# untitled.net
KiCad netlist of a schematic drawn in EAGLE
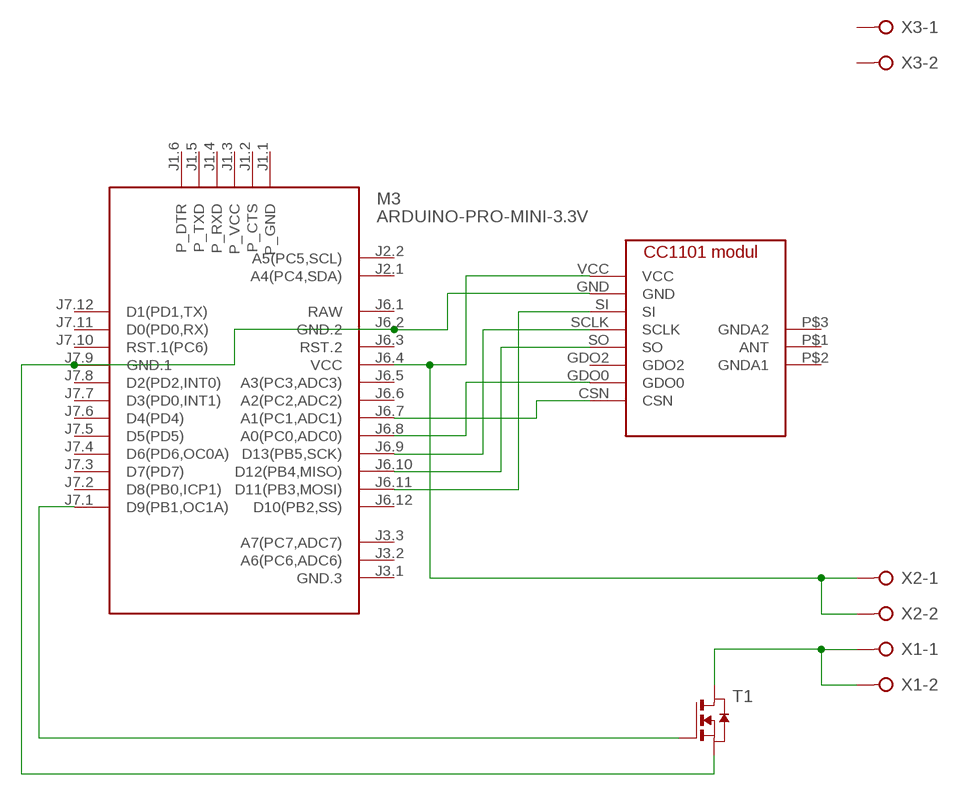
[diagram p0: schematic, sheet 1]

(export (version "E")
  (design (tool "Eeschema 10.0.6"))
  (components
    (comp (ref "M3")
      (value "ARDUINO-PRO-MINI-3.3V")
      (footprint "eagle-import:ARDUINO-PRO-MINI")
      (libsource (lib "eagle-import") (part "ARDUINO-PRO-MINI-3.3V"))
    )
    (comp (ref "T1")
      (value "NMOSSOT23")
      (footprint "eagle-import:SOT-23")
      (libsource (lib "eagle-import") (part "NMOSSOT23"))
    )
    (comp (ref "U$1")
      (value "CC1101-MODULEPFOSTEN")
      (footprint "eagle-import:PFOSTEN")
      (libsource (lib "eagle-import") (part "CC1101-MODULEPFOSTEN"))
    )
    (comp (ref "X1")
      (value "W237-02P")
      (footprint "eagle-import:W237-132")
      (libsource (lib "eagle-import") (part "W237-02P"))
    )
    (comp (ref "X2")
      (value "W237-02P")
      (footprint "eagle-import:W237-132")
      (libsource (lib "eagle-import") (part "W237-02P"))
    )
    (comp (ref "X3")
      (value "W237-02P")
      (footprint "eagle-import:W237-132")
      (libsource (lib "eagle-import") (part "W237-02P"))
    )
  )
  (nets
    (net (code "1") (name "/RAW") (class "Default")
      (node (ref "M3") (pin "J6.1") (pinfunction "RAW_J6.1") (pintype "power_in"))
    )
    (net (code "2") (name "Net-(M3-A0(PC0,ADC0))") (class "Default")
      (node (ref "M3") (pin "J6.8") (pinfunction "A0(PC0,ADC0)_J6.8") (pintype "bidirectional"))
      (node (ref "U$1") (pin "GDO0") (pinfunction "GDO0_GDO0") (pintype "output"))
    )
    (net (code "3") (name "Net-(M3-A1(PC1,ADC1))") (class "Default")
      (node (ref "M3") (pin "J6.7") (pinfunction "A1(PC1,ADC1)_J6.7") (pintype "bidirectional"))
      (node (ref "U$1") (pin "CSN") (pinfunction "CSN_CSN") (pintype "input"))
    )
    (net (code "4") (name "Net-(M3-D9(PB1,OC1A))") (class "Default")
      (node (ref "M3") (pin "J7.1") (pinfunction "D9(PB1,OC1A)_J7.1") (pintype "bidirectional"))
      (node (ref "T1") (pin "3") (pinfunction "G_3") (pintype "passive"))
    )
    (net (code "5") (name "Net-(M3-D11(PB3,MOSI))") (class "Default")
      (node (ref "M3") (pin "J6.11") (pinfunction "D11(PB3,MOSI)_J6.11") (pintype "bidirectional"))
      (node (ref "U$1") (pin "SI") (pinfunction "SI_SI") (pintype "input"))
    )
    (net (code "6") (name "Net-(M3-D12(PB4,MISO))") (class "Default")
      (node (ref "M3") (pin "J6.10") (pinfunction "D12(PB4,MISO)_J6.10") (pintype "bidirectional"))
      (node (ref "U$1") (pin "SO") (pinfunction "SO_SO") (pintype "output"))
    )
    (net (code "7") (name "Net-(M3-D13(PB5,SCK))") (class "Default")
      (node (ref "M3") (pin "J6.9") (pinfunction "D13(PB5,SCK)_J6.9") (pintype "bidirectional"))
      (node (ref "U$1") (pin "SCLK") (pinfunction "SCLK_SCLK") (pintype "input"))
    )
    (net (code "8") (name "Net-(M3-GND.1)") (class "Default")
      (node (ref "M3") (pin "J6.2") (pinfunction "GND.2_J6.2") (pintype "power_in"))
      (node (ref "M3") (pin "J7.9") (pinfunction "GND.1_J7.9") (pintype "power_in"))
      (node (ref "T1") (pin "2") (pinfunction "S_2") (pintype "passive"))
      (node (ref "U$1") (pin "GND") (pinfunction "GND_GND") (pintype "power_in"))
    )
    (net (code "9") (name "Net-(M3-VCC)") (class "Default")
      (node (ref "M3") (pin "J6.4") (pinfunction "VCC_J6.4") (pintype "power_in"))
      (node (ref "U$1") (pin "VCC") (pinfunction "VCC_VCC") (pintype "power_in"))
      (node (ref "X2") (pin "1") (pinfunction "KL_1") (pintype "passive"))
      (node (ref "X2") (pin "2") (pinfunction "KL_2") (pintype "passive"))
    )
    (net (code "10") (name "Net-(T1-D)") (class "Default")
      (node (ref "T1") (pin "1") (pinfunction "D_1") (pintype "passive"))
      (node (ref "X1") (pin "1") (pinfunction "KL_1") (pintype "passive"))
      (node (ref "X1") (pin "2") (pinfunction "KL_2") (pintype "passive"))
    )
    (net (code "11") (name "unconnected-(M3-A2(PC2,ADC2)-PadJ6.6)") (class "Default")
      (node (ref "M3") (pin "J6.6") (pinfunction "A2(PC2,ADC2)_J6.6") (pintype "bidirectional"))
    )
    (net (code "12") (name "unconnected-(M3-A3(PC3,ADC3)-PadJ6.5)") (class "Default")
      (node (ref "M3") (pin "J6.5") (pinfunction "A3(PC3,ADC3)_J6.5") (pintype "bidirectional"))
    )
    (net (code "13") (name "unconnected-(M3-A4(PC4,SDA)-PadJ2.1)") (class "Default")
      (node (ref "M3") (pin "J2.1") (pinfunction "A4(PC4,SDA)_J2.1") (pintype "bidirectional"))
    )
    (net (code "14") (name "unconnected-(M3-A5(PC5,SCL)-PadJ2.2)") (class "Default")
      (node (ref "M3") (pin "J2.2") (pinfunction "A5(PC5,SCL)_J2.2") (pintype "bidirectional"))
    )
    (net (code "15") (name "unconnected-(M3-A6(PC6,ADC6)-PadJ3.2)") (class "Default")
      (node (ref "M3") (pin "J3.2") (pinfunction "A6(PC6,ADC6)_J3.2") (pintype "bidirectional"))
    )
    (net (code "16") (name "unconnected-(M3-A7(PC7,ADC7)-PadJ3.3)") (class "Default")
      (node (ref "M3") (pin "J3.3") (pinfunction "A7(PC7,ADC7)_J3.3") (pintype "bidirectional"))
    )
    (net (code "17") (name "unconnected-(M3-D0(PD0,RX)-PadJ7.11)") (class "Default")
      (node (ref "M3") (pin "J7.11") (pinfunction "D0(PD0,RX)_J7.11") (pintype "bidirectional"))
    )
    (net (code "18") (name "unconnected-(M3-D1(PD1,TX)-PadJ7.12)") (class "Default")
      (node (ref "M3") (pin "J7.12") (pinfunction "D1(PD1,TX)_J7.12") (pintype "bidirectional"))
    )
    (net (code "19") (name "unconnected-(M3-D2(PD2,INT0)-PadJ7.8)") (class "Default")
      (node (ref "M3") (pin "J7.8") (pinfunction "D2(PD2,INT0)_J7.8") (pintype "bidirectional"))
    )
    (net (code "20") (name "unconnected-(M3-D3(PD0,INT1)-PadJ7.7)") (class "Default")
      (node (ref "M3") (pin "J7.7") (pinfunction "D3(PD0,INT1)_J7.7") (pintype "bidirectional"))
    )
    (net (code "21") (name "unconnected-(M3-D4(PD4)-PadJ7.6)") (class "Default")
      (node (ref "M3") (pin "J7.6") (pinfunction "D4(PD4)_J7.6") (pintype "bidirectional"))
    )
    (net (code "22") (name "unconnected-(M3-D5(PD5)-PadJ7.5)") (class "Default")
      (node (ref "M3") (pin "J7.5") (pinfunction "D5(PD5)_J7.5") (pintype "bidirectional"))
    )
    (net (code "23") (name "unconnected-(M3-D6(PD6,OC0A)-PadJ7.4)") (class "Default")
      (node (ref "M3") (pin "J7.4") (pinfunction "D6(PD6,OC0A)_J7.4") (pintype "bidirectional"))
    )
    (net (code "24") (name "unconnected-(M3-D7(PD7)-PadJ7.3)") (class "Default")
      (node (ref "M3") (pin "J7.3") (pinfunction "D7(PD7)_J7.3") (pintype "bidirectional"))
    )
    (net (code "25") (name "unconnected-(M3-D8(PB0,ICP1)-PadJ7.2)") (class "Default")
      (node (ref "M3") (pin "J7.2") (pinfunction "D8(PB0,ICP1)_J7.2") (pintype "bidirectional"))
    )
    (net (code "26") (name "unconnected-(M3-D10(PB2,SS)-PadJ6.12)") (class "Default")
      (node (ref "M3") (pin "J6.12") (pinfunction "D10(PB2,SS)_J6.12") (pintype "bidirectional"))
    )
    (net (code "27") (name "unconnected-(M3-GND.3-PadJ3.1)") (class "Default")
      (node (ref "M3") (pin "J3.1") (pinfunction "GND.3_J3.1") (pintype "bidirectional"))
    )
    (net (code "28") (name "unconnected-(M3-P_CTS-PadJ1.2)") (class "Default")
      (node (ref "M3") (pin "J1.2") (pinfunction "P_CTS_J1.2") (pintype "bidirectional"))
    )
    (net (code "29") (name "unconnected-(M3-P_DTR-PadJ1.6)") (class "Default")
      (node (ref "M3") (pin "J1.6") (pinfunction "P_DTR_J1.6") (pintype "bidirectional"))
    )
    (net (code "30") (name "unconnected-(M3-P_GND-PadJ1.1)") (class "Default")
      (node (ref "M3") (pin "J1.1") (pinfunction "P_GND_J1.1") (pintype "bidirectional"))
    )
    (net (code "31") (name "unconnected-(M3-P_RXD-PadJ1.4)") (class "Default")
      (node (ref "M3") (pin "J1.4") (pinfunction "P_RXD_J1.4") (pintype "bidirectional"))
    )
    (net (code "32") (name "unconnected-(M3-P_TXD-PadJ1.5)") (class "Default")
      (node (ref "M3") (pin "J1.5") (pinfunction "P_TXD_J1.5") (pintype "bidirectional"))
    )
    (net (code "33") (name "unconnected-(M3-P_VCC-PadJ1.3)") (class "Default")
      (node (ref "M3") (pin "J1.3") (pinfunction "P_VCC_J1.3") (pintype "bidirectional"))
    )
    (net (code "34") (name "unconnected-(M3-RST.1(PC6)-PadJ7.10)") (class "Default")
      (node (ref "M3") (pin "J7.10") (pinfunction "RST.1(PC6)_J7.10") (pintype "bidirectional"))
    )
    (net (code "35") (name "unconnected-(M3-RST.2-PadJ6.3)") (class "Default")
      (node (ref "M3") (pin "J6.3") (pinfunction "RST.2_J6.3") (pintype "bidirectional"))
    )
    (net (code "36") (name "unconnected-(U$1-ANT-PadP$1)") (class "Default")
      (node (ref "U$1") (pin "P$1") (pinfunction "ANT_P$1") (pintype "bidirectional"))
    )
    (net (code "37") (name "unconnected-(U$1-GNDA1-PadP$2)") (class "Default")
      (node (ref "U$1") (pin "P$2") (pinfunction "GNDA1_P$2") (pintype "bidirectional"))
    )
    (net (code "38") (name "unconnected-(U$1-GNDA2-PadP$3)") (class "Default")
      (node (ref "U$1") (pin "P$3") (pinfunction "GNDA2_P$3") (pintype "bidirectional"))
    )
    (net (code "39") (name "unconnected-(U$1-PadGDO2)") (class "Default")
      (node (ref "U$1") (pin "GDO2") (pinfunction "GDO2_GDO2") (pintype "output"))
    )
    (net (code "40") (name "unconnected-(X3A-KL-Pad1)") (class "Default")
      (node (ref "X3") (pin "1") (pinfunction "KL_1") (pintype "passive"))
    )
    (net (code "41") (name "unconnected-(X3B-KL-Pad2)") (class "Default")
      (node (ref "X3") (pin "2") (pinfunction "KL_2") (pintype "passive"))
    )
  )
)
